# Vref_2v5.net
KiCad netlist of a schematic drawn in Altium Designer
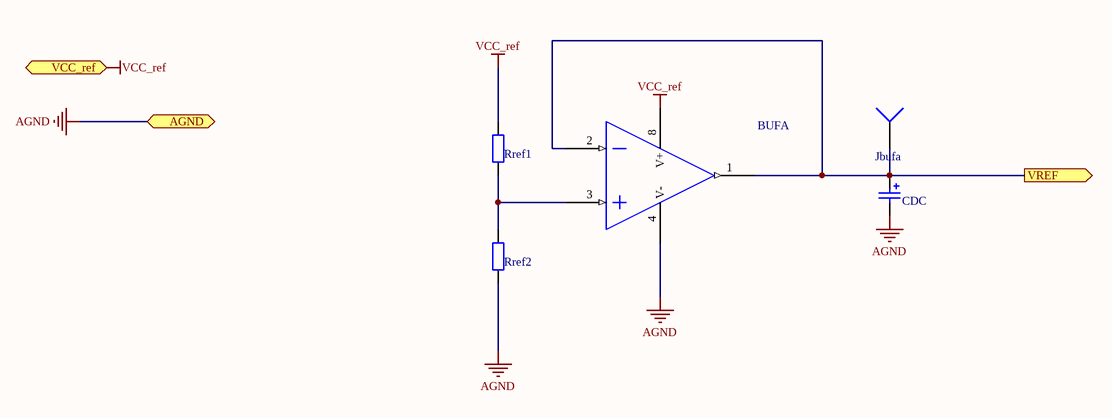
[diagram p0: Vref_2v5.SchDoc]

(export (version "E")
  (design (tool "Eeschema 10.0.6"))
  (components
    (comp (ref "BUF")
      (value "LT6221")
      (footprint "ECE-SO8")
      (description "IC OPAMP LT6221 DUAL SM")
      (libsource (lib "OpAmps$") (part "OPA000102"))
    )
    (comp (ref "CDC")
      (value "10uF")
      (footprint "ECE-CAPAE4X5.4SM")
      (description "CAP 10uF 16V ELE SM")
      (libsource (lib "Capacitos$") (part "CAP000303"))
    )
    (comp (ref "Jbufa")
      (value "TEST PIN")
      (footprint "ECE-HDR1TH")
      (libsource (lib "Connectors$") (part "CON000017"))
    )
    (comp (ref "Rref1")
      (value "47K")
      (footprint "ECE-RESC1608-0603SM")
      (description "RES CER 47K 1608 SM")
      (libsource (lib "Resistors$") (part "RES000158"))
    )
    (comp (ref "Rref2")
      (value "47K")
      (footprint "ECE-RESC1608-0603SM")
      (description "RES CER 47K 1608 SM")
      (libsource (lib "Resistors$") (part "RES000158"))
    )
  )
  (nets
    (net (code "1") (name "/VREF") (class "Default")
      (node (ref "BUF") (pin "1") (pinfunction "OUT1_1") (pintype "output"))
      (node (ref "BUF") (pin "2") (pinfunction "IN1(-)_2") (pintype "input"))
      (node (ref "CDC") (pin "1") (pinfunction "1_1") (pintype "passive"))
      (node (ref "Jbufa") (pin "1") (pinfunction "1_1") (pintype "passive"))
    )
    (net (code "2") (name "AGND") (class "Default")
      (node (ref "BUF") (pin "4") (pinfunction "V-_4") (pintype "power_in"))
      (node (ref "CDC") (pin "2") (pinfunction "2_2") (pintype "passive"))
      (node (ref "Rref2") (pin "1") (pinfunction "1_1") (pintype "passive"))
    )
    (net (code "3") (name "Net-(BUFA-IN1(+))") (class "Default")
      (node (ref "BUF") (pin "3") (pinfunction "IN1(+)_3") (pintype "input"))
      (node (ref "Rref1") (pin "1") (pinfunction "1_1") (pintype "passive"))
      (node (ref "Rref2") (pin "2") (pinfunction "2_2") (pintype "passive"))
    )
    (net (code "4") (name "VCC_ref") (class "Default")
      (node (ref "BUF") (pin "8") (pinfunction "V+_8") (pintype "power_in"))
      (node (ref "Rref1") (pin "2") (pinfunction "2_2") (pintype "passive"))
    )
  )
)
